# mycpu_monitor.net
KiCad netlist of a schematic drawn in EAGLE
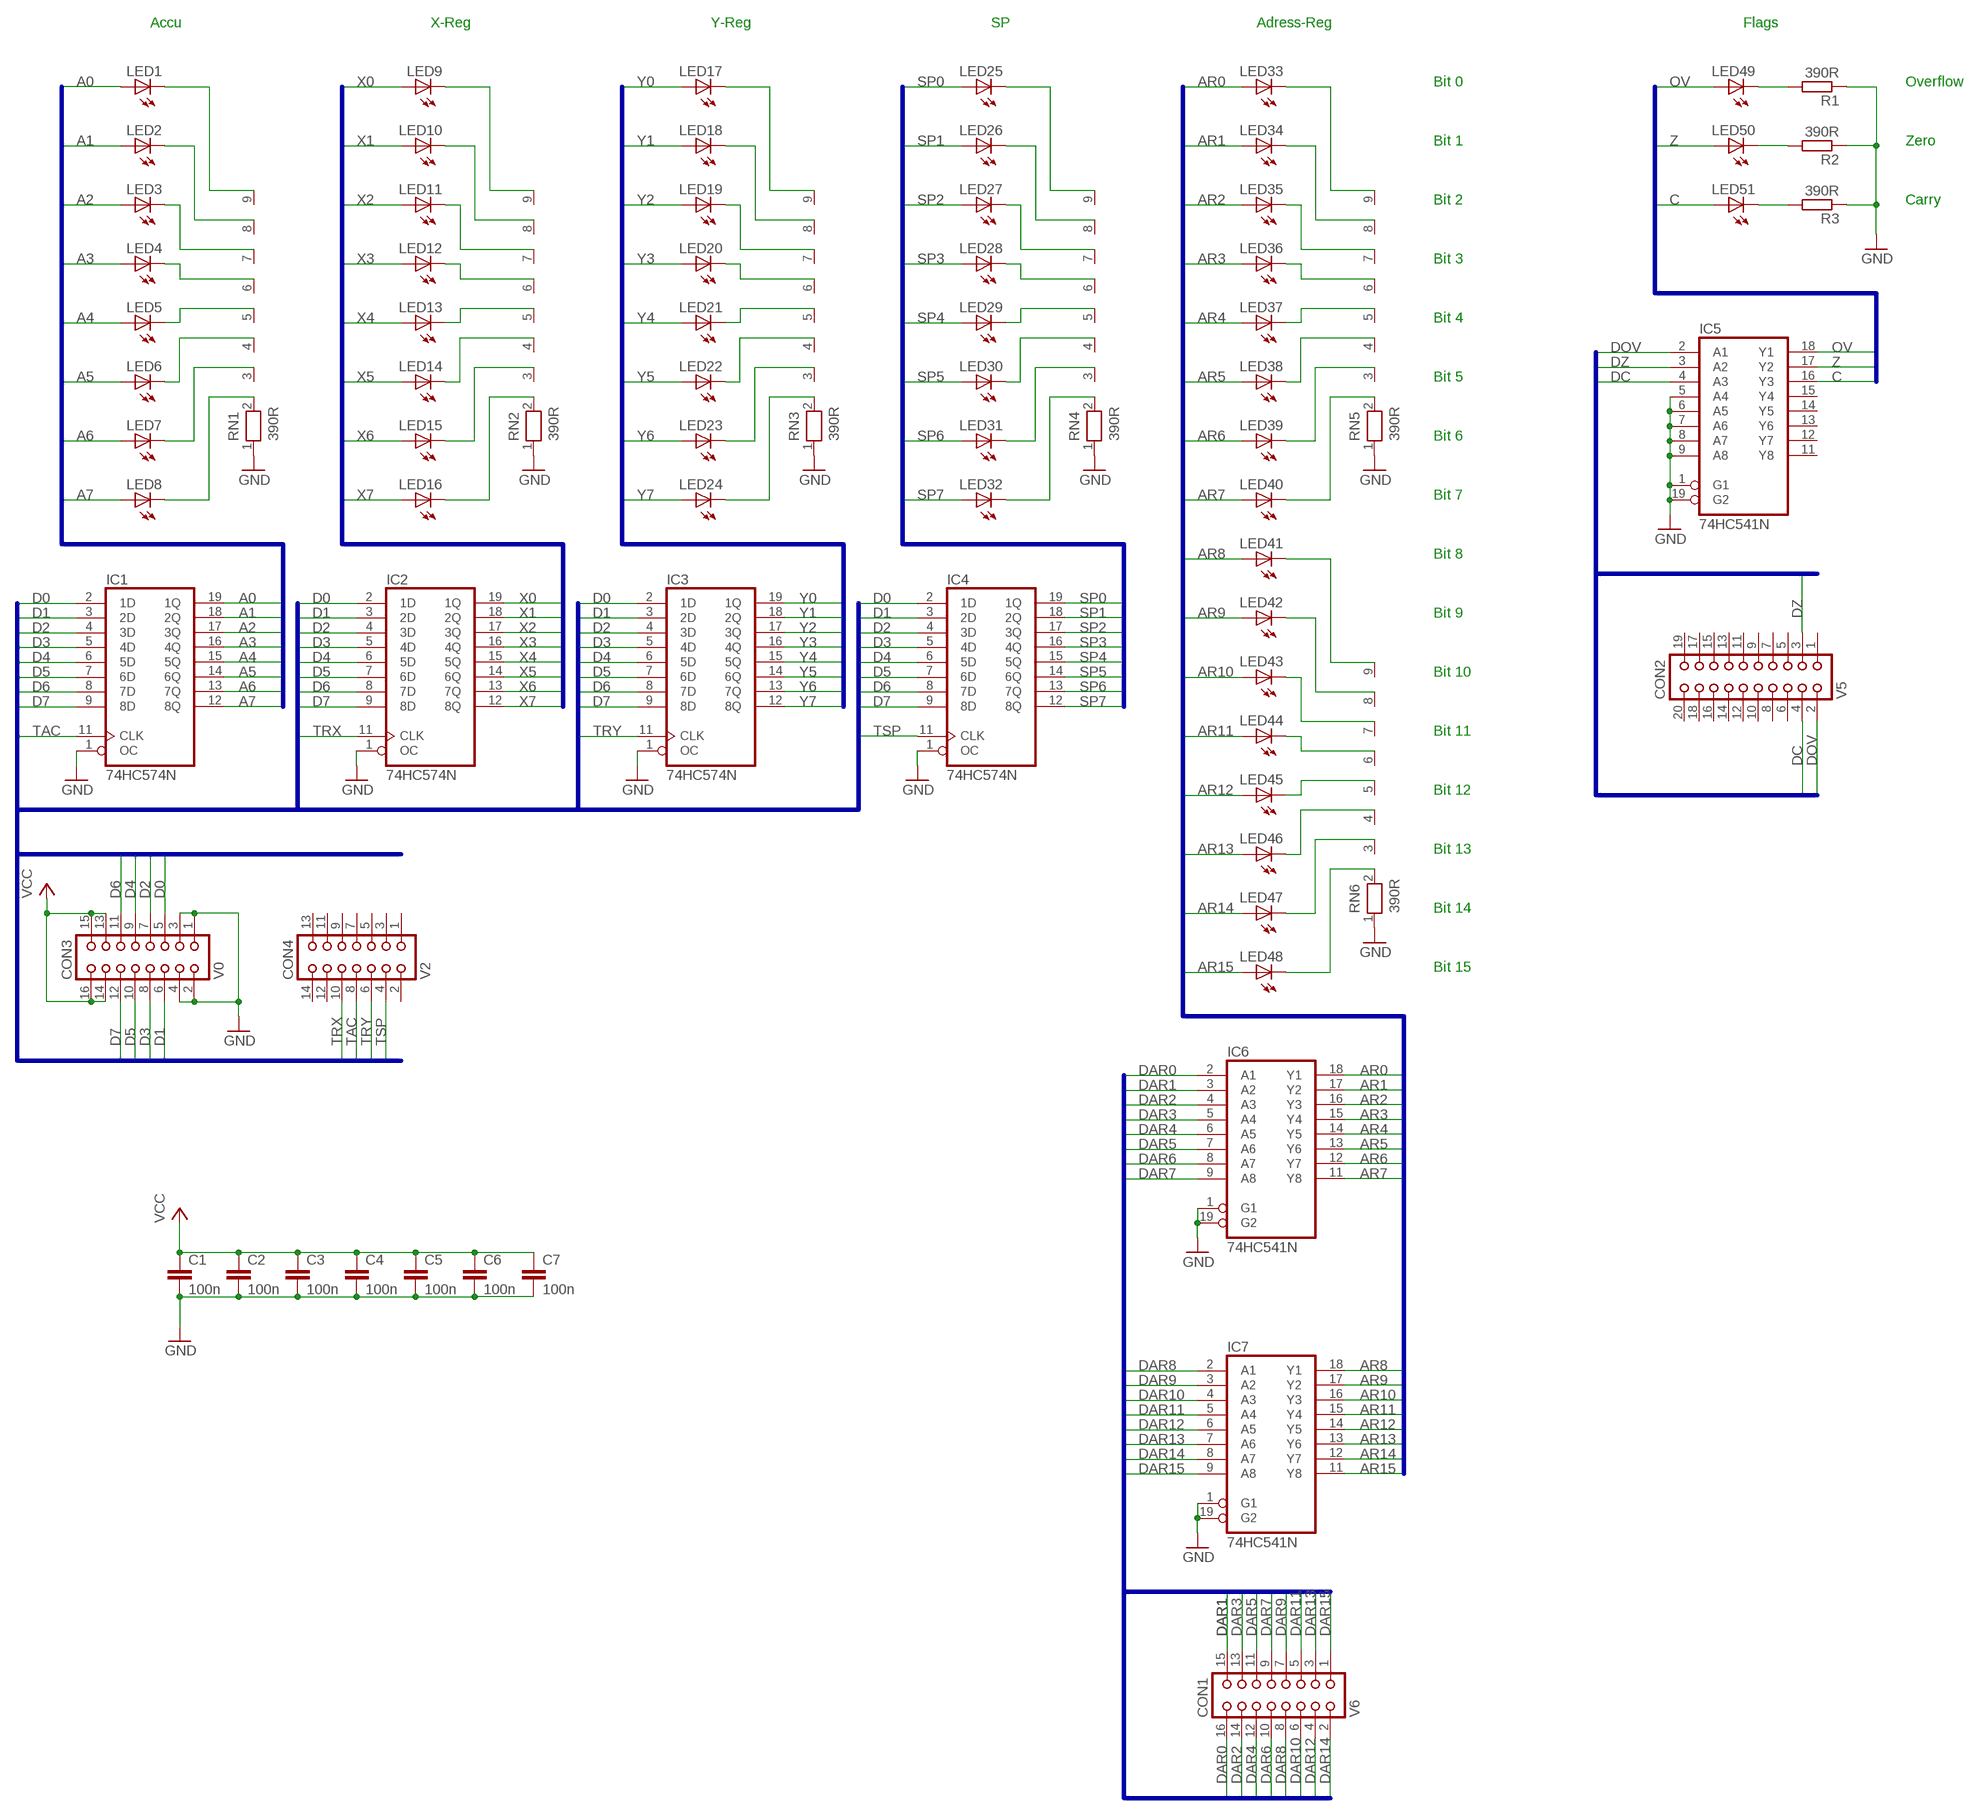
[diagram p0: schematic, sheet 1]

(export (version "E")
  (design (tool "Eeschema 10.0.6"))
  (components
    (comp (ref "C1")
      (value "100n")
      (footprint "eagle-import:C050-024X044")
      (libsource (lib "eagle-import") (part "C-EU050-024X044"))
    )
    (comp (ref "C2")
      (value "100n")
      (footprint "eagle-import:C050-024X044")
      (libsource (lib "eagle-import") (part "C-EU050-024X044"))
    )
    (comp (ref "C3")
      (value "100n")
      (footprint "eagle-import:C050-024X044")
      (libsource (lib "eagle-import") (part "C-EU050-024X044"))
    )
    (comp (ref "C4")
      (value "100n")
      (footprint "eagle-import:C050-024X044")
      (libsource (lib "eagle-import") (part "C-EU050-024X044"))
    )
    (comp (ref "C5")
      (value "100n")
      (footprint "eagle-import:C050-024X044")
      (libsource (lib "eagle-import") (part "C-EU050-024X044"))
    )
    (comp (ref "C6")
      (value "100n")
      (footprint "eagle-import:C050-024X044")
      (libsource (lib "eagle-import") (part "C-EU050-024X044"))
    )
    (comp (ref "C7")
      (value "100n")
      (footprint "eagle-import:C050-024X044")
      (libsource (lib "eagle-import") (part "C-EU050-024X044"))
    )
    (comp (ref "CON1")
      (value "V6")
      (footprint "eagle-import:CON16L")
      (libsource (lib "eagle-import") (part "CON16L"))
    )
    (comp (ref "CON2")
      (value "V5")
      (footprint "eagle-import:CON20L")
      (libsource (lib "eagle-import") (part "CON20L"))
    )
    (comp (ref "CON3")
      (value "V0")
      (footprint "eagle-import:CON16L")
      (libsource (lib "eagle-import") (part "CON16L"))
    )
    (comp (ref "CON4")
      (value "V2")
      (footprint "eagle-import:CON14L")
      (libsource (lib "eagle-import") (part "CON14L"))
    )
    (comp (ref "IC1")
      (value "74HC574N")
      (footprint "eagle-import:DIL20")
      (libsource (lib "eagle-import") (part "74574NHC"))
    )
    (comp (ref "IC2")
      (value "74HC574N")
      (footprint "eagle-import:DIL20")
      (libsource (lib "eagle-import") (part "74574NHC"))
    )
    (comp (ref "IC3")
      (value "74HC574N")
      (footprint "eagle-import:DIL20")
      (libsource (lib "eagle-import") (part "74574NHC"))
    )
    (comp (ref "IC4")
      (value "74HC574N")
      (footprint "eagle-import:DIL20")
      (libsource (lib "eagle-import") (part "74574NHC"))
    )
    (comp (ref "IC5")
      (value "74HC541N")
      (footprint "eagle-import:DIL20")
      (libsource (lib "eagle-import") (part "74541NHC"))
    )
    (comp (ref "IC6")
      (value "74HC541N")
      (footprint "eagle-import:DIL20")
      (libsource (lib "eagle-import") (part "74541NHC"))
    )
    (comp (ref "IC7")
      (value "74HC541N")
      (footprint "eagle-import:DIL20")
      (libsource (lib "eagle-import") (part "74541NHC"))
    )
    (comp (ref "LED1")
      (value "LED3MM")
      (footprint "eagle-import:LED3MM")
      (libsource (lib "eagle-import") (part "LED3MM"))
    )
    (comp (ref "LED2")
      (value "LED3MM")
      (footprint "eagle-import:LED3MM")
      (libsource (lib "eagle-import") (part "LED3MM"))
    )
    (comp (ref "LED3")
      (value "LED3MM")
      (footprint "eagle-import:LED3MM")
      (libsource (lib "eagle-import") (part "LED3MM"))
    )
    (comp (ref "LED4")
      (value "LED3MM")
      (footprint "eagle-import:LED3MM")
      (libsource (lib "eagle-import") (part "LED3MM"))
    )
    (comp (ref "LED5")
      (value "LED3MM")
      (footprint "eagle-import:LED3MM")
      (libsource (lib "eagle-import") (part "LED3MM"))
    )
    (comp (ref "LED6")
      (value "LED3MM")
      (footprint "eagle-import:LED3MM")
      (libsource (lib "eagle-import") (part "LED3MM"))
    )
    (comp (ref "LED7")
      (value "LED3MM")
      (footprint "eagle-import:LED3MM")
      (libsource (lib "eagle-import") (part "LED3MM"))
    )
    (comp (ref "LED8")
      (value "LED3MM")
      (footprint "eagle-import:LED3MM")
      (libsource (lib "eagle-import") (part "LED3MM"))
    )
    (comp (ref "LED9")
      (value "LED3MM")
      (footprint "eagle-import:LED3MM")
      (libsource (lib "eagle-import") (part "LED3MM"))
    )
    (comp (ref "LED10")
      (value "LED3MM")
      (footprint "eagle-import:LED3MM")
      (libsource (lib "eagle-import") (part "LED3MM"))
    )
    (comp (ref "LED11")
      (value "LED3MM")
      (footprint "eagle-import:LED3MM")
      (libsource (lib "eagle-import") (part "LED3MM"))
    )
    (comp (ref "LED12")
      (value "LED3MM")
      (footprint "eagle-import:LED3MM")
      (libsource (lib "eagle-import") (part "LED3MM"))
    )
    (comp (ref "LED13")
      (value "LED3MM")
      (footprint "eagle-import:LED3MM")
      (libsource (lib "eagle-import") (part "LED3MM"))
    )
    (comp (ref "LED14")
      (value "LED3MM")
      (footprint "eagle-import:LED3MM")
      (libsource (lib "eagle-import") (part "LED3MM"))
    )
    (comp (ref "LED15")
      (value "LED3MM")
      (footprint "eagle-import:LED3MM")
      (libsource (lib "eagle-import") (part "LED3MM"))
    )
    (comp (ref "LED16")
      (value "LED3MM")
      (footprint "eagle-import:LED3MM")
      (libsource (lib "eagle-import") (part "LED3MM"))
    )
    (comp (ref "LED17")
      (value "LED3MM")
      (footprint "eagle-import:LED3MM")
      (libsource (lib "eagle-import") (part "LED3MM"))
    )
    (comp (ref "LED18")
      (value "LED3MM")
      (footprint "eagle-import:LED3MM")
      (libsource (lib "eagle-import") (part "LED3MM"))
    )
    (comp (ref "LED19")
      (value "LED3MM")
      (footprint "eagle-import:LED3MM")
      (libsource (lib "eagle-import") (part "LED3MM"))
    )
    (comp (ref "LED20")
      (value "LED3MM")
      (footprint "eagle-import:LED3MM")
      (libsource (lib "eagle-import") (part "LED3MM"))
    )
    (comp (ref "LED21")
      (value "LED3MM")
      (footprint "eagle-import:LED3MM")
      (libsource (lib "eagle-import") (part "LED3MM"))
    )
    (comp (ref "LED22")
      (value "LED3MM")
      (footprint "eagle-import:LED3MM")
      (libsource (lib "eagle-import") (part "LED3MM"))
    )
    (comp (ref "LED23")
      (value "LED3MM")
      (footprint "eagle-import:LED3MM")
      (libsource (lib "eagle-import") (part "LED3MM"))
    )
    (comp (ref "LED24")
      (value "LED3MM")
      (footprint "eagle-import:LED3MM")
      (libsource (lib "eagle-import") (part "LED3MM"))
    )
    (comp (ref "LED25")
      (value "LED3MM")
      (footprint "eagle-import:LED3MM")
      (libsource (lib "eagle-import") (part "LED3MM"))
    )
    (comp (ref "LED26")
      (value "LED3MM")
      (footprint "eagle-import:LED3MM")
      (libsource (lib "eagle-import") (part "LED3MM"))
    )
    (comp (ref "LED27")
      (value "LED3MM")
      (footprint "eagle-import:LED3MM")
      (libsource (lib "eagle-import") (part "LED3MM"))
    )
    (comp (ref "LED28")
      (value "LED3MM")
      (footprint "eagle-import:LED3MM")
      (libsource (lib "eagle-import") (part "LED3MM"))
    )
    (comp (ref "LED29")
      (value "LED3MM")
      (footprint "eagle-import:LED3MM")
      (libsource (lib "eagle-import") (part "LED3MM"))
    )
    (comp (ref "LED30")
      (value "LED3MM")
      (footprint "eagle-import:LED3MM")
      (libsource (lib "eagle-import") (part "LED3MM"))
    )
    (comp (ref "LED31")
      (value "LED3MM")
      (footprint "eagle-import:LED3MM")
      (libsource (lib "eagle-import") (part "LED3MM"))
    )
    (comp (ref "LED32")
      (value "LED3MM")
      (footprint "eagle-import:LED3MM")
      (libsource (lib "eagle-import") (part "LED3MM"))
    )
    (comp (ref "LED33")
      (value "LED3MM")
      (footprint "eagle-import:LED3MM")
      (libsource (lib "eagle-import") (part "LED3MM"))
    )
    (comp (ref "LED34")
      (value "LED3MM")
      (footprint "eagle-import:LED3MM")
      (libsource (lib "eagle-import") (part "LED3MM"))
    )
    (comp (ref "LED35")
      (value "LED3MM")
      (footprint "eagle-import:LED3MM")
      (libsource (lib "eagle-import") (part "LED3MM"))
    )
    (comp (ref "LED36")
      (value "LED3MM")
      (footprint "eagle-import:LED3MM")
      (libsource (lib "eagle-import") (part "LED3MM"))
    )
    (comp (ref "LED37")
      (value "LED3MM")
      (footprint "eagle-import:LED3MM")
      (libsource (lib "eagle-import") (part "LED3MM"))
    )
    (comp (ref "LED38")
      (value "LED3MM")
      (footprint "eagle-import:LED3MM")
      (libsource (lib "eagle-import") (part "LED3MM"))
    )
    (comp (ref "LED39")
      (value "LED3MM")
      (footprint "eagle-import:LED3MM")
      (libsource (lib "eagle-import") (part "LED3MM"))
    )
    (comp (ref "LED40")
      (value "LED3MM")
      (footprint "eagle-import:LED3MM")
      (libsource (lib "eagle-import") (part "LED3MM"))
    )
    (comp (ref "LED41")
      (value "LED3MM")
      (footprint "eagle-import:LED3MM")
      (libsource (lib "eagle-import") (part "LED3MM"))
    )
    (comp (ref "LED42")
      (value "LED3MM")
      (footprint "eagle-import:LED3MM")
      (libsource (lib "eagle-import") (part "LED3MM"))
    )
    (comp (ref "LED43")
      (value "LED3MM")
      (footprint "eagle-import:LED3MM")
      (libsource (lib "eagle-import") (part "LED3MM"))
    )
    (comp (ref "LED44")
      (value "LED3MM")
      (footprint "eagle-import:LED3MM")
      (libsource (lib "eagle-import") (part "LED3MM"))
    )
    (comp (ref "LED45")
      (value "LED3MM")
      (footprint "eagle-import:LED3MM")
      (libsource (lib "eagle-import") (part "LED3MM"))
    )
    (comp (ref "LED46")
      (value "LED3MM")
      (footprint "eagle-import:LED3MM")
      (libsource (lib "eagle-import") (part "LED3MM"))
    )
    (comp (ref "LED47")
      (value "LED3MM")
      (footprint "eagle-import:LED3MM")
      (libsource (lib "eagle-import") (part "LED3MM"))
    )
    (comp (ref "LED48")
      (value "LED3MM")
      (footprint "eagle-import:LED3MM")
      (libsource (lib "eagle-import") (part "LED3MM"))
    )
    (comp (ref "LED49")
      (value "LED3MM")
      (footprint "eagle-import:LED3MM")
      (libsource (lib "eagle-import") (part "LED3MM"))
    )
    (comp (ref "LED50")
      (value "LED3MM")
      (footprint "eagle-import:LED3MM")
      (libsource (lib "eagle-import") (part "LED3MM"))
    )
    (comp (ref "LED51")
      (value "LED3MM")
      (footprint "eagle-import:LED3MM")
      (libsource (lib "eagle-import") (part "LED3MM"))
    )
    (comp (ref "R1")
      (value "390R")
      (footprint "eagle-import:0207_7")
      (libsource (lib "eagle-import") (part "R-EU_0207/7"))
    )
    (comp (ref "R2")
      (value "390R")
      (footprint "eagle-import:0207_7")
      (libsource (lib "eagle-import") (part "R-EU_0207/7"))
    )
    (comp (ref "R3")
      (value "390R")
      (footprint "eagle-import:0207_7")
      (libsource (lib "eagle-import") (part "R-EU_0207/7"))
    )
    (comp (ref "RN1")
      (value "390R")
      (footprint "eagle-import:RN-9")
      (libsource (lib "eagle-import") (part "RN08"))
    )
    (comp (ref "RN2")
      (value "390R")
      (footprint "eagle-import:RN-9")
      (libsource (lib "eagle-import") (part "RN08"))
    )
    (comp (ref "RN3")
      (value "390R")
      (footprint "eagle-import:RN-9")
      (libsource (lib "eagle-import") (part "RN08"))
    )
    (comp (ref "RN4")
      (value "390R")
      (footprint "eagle-import:RN-9")
      (libsource (lib "eagle-import") (part "RN08"))
    )
    (comp (ref "RN5")
      (value "390R")
      (footprint "eagle-import:RN-9")
      (libsource (lib "eagle-import") (part "RN08"))
    )
    (comp (ref "RN6")
      (value "390R")
      (footprint "eagle-import:RN-9")
      (libsource (lib "eagle-import") (part "RN08"))
    )
  )
  (nets
    (net (code "1") (name "/A0") (class "Default")
      (node (ref "IC1") (pin "19") (pinfunction "1Q_19") (pintype "tri_state"))
      (node (ref "LED1") (pin "A") (pinfunction "A_A") (pintype "passive"))
    )
    (net (code "2") (name "/A1") (class "Default")
      (node (ref "IC1") (pin "18") (pinfunction "2Q_18") (pintype "tri_state"))
      (node (ref "LED2") (pin "A") (pinfunction "A_A") (pintype "passive"))
    )
    (net (code "3") (name "/A2") (class "Default")
      (node (ref "IC1") (pin "17") (pinfunction "3Q_17") (pintype "tri_state"))
      (node (ref "LED3") (pin "A") (pinfunction "A_A") (pintype "passive"))
    )
    (net (code "4") (name "/A3") (class "Default")
      (node (ref "IC1") (pin "16") (pinfunction "4Q_16") (pintype "tri_state"))
      (node (ref "LED4") (pin "A") (pinfunction "A_A") (pintype "passive"))
    )
    (net (code "5") (name "/A4") (class "Default")
      (node (ref "IC1") (pin "15") (pinfunction "5Q_15") (pintype "tri_state"))
      (node (ref "LED5") (pin "A") (pinfunction "A_A") (pintype "passive"))
    )
    (net (code "6") (name "/A5") (class "Default")
      (node (ref "IC1") (pin "14") (pinfunction "6Q_14") (pintype "tri_state"))
      (node (ref "LED6") (pin "A") (pinfunction "A_A") (pintype "passive"))
    )
    (net (code "7") (name "/A6") (class "Default")
      (node (ref "IC1") (pin "13") (pinfunction "7Q_13") (pintype "tri_state"))
      (node (ref "LED7") (pin "A") (pinfunction "A_A") (pintype "passive"))
    )
    (net (code "8") (name "/A7") (class "Default")
      (node (ref "IC1") (pin "12") (pinfunction "8Q_12") (pintype "tri_state"))
      (node (ref "LED8") (pin "A") (pinfunction "A_A") (pintype "passive"))
    )
    (net (code "9") (name "/AR0") (class "Default")
      (node (ref "IC6") (pin "18") (pinfunction "Y1_18") (pintype "tri_state"))
      (node (ref "LED33") (pin "A") (pinfunction "A_A") (pintype "passive"))
    )
    (net (code "10") (name "/AR1") (class "Default")
      (node (ref "IC6") (pin "17") (pinfunction "Y2_17") (pintype "tri_state"))
      (node (ref "LED34") (pin "A") (pinfunction "A_A") (pintype "passive"))
    )
    (net (code "11") (name "/AR2") (class "Default")
      (node (ref "IC6") (pin "16") (pinfunction "Y3_16") (pintype "tri_state"))
      (node (ref "LED35") (pin "A") (pinfunction "A_A") (pintype "passive"))
    )
    (net (code "12") (name "/AR3") (class "Default")
      (node (ref "IC6") (pin "15") (pinfunction "Y4_15") (pintype "tri_state"))
      (node (ref "LED36") (pin "A") (pinfunction "A_A") (pintype "passive"))
    )
    (net (code "13") (name "/AR4") (class "Default")
      (node (ref "IC6") (pin "14") (pinfunction "Y5_14") (pintype "tri_state"))
      (node (ref "LED37") (pin "A") (pinfunction "A_A") (pintype "passive"))
    )
    (net (code "14") (name "/AR5") (class "Default")
      (node (ref "IC6") (pin "13") (pinfunction "Y6_13") (pintype "tri_state"))
      (node (ref "LED38") (pin "A") (pinfunction "A_A") (pintype "passive"))
    )
    (net (code "15") (name "/AR6") (class "Default")
      (node (ref "IC6") (pin "12") (pinfunction "Y7_12") (pintype "tri_state"))
      (node (ref "LED39") (pin "A") (pinfunction "A_A") (pintype "passive"))
    )
    (net (code "16") (name "/AR7") (class "Default")
      (node (ref "IC6") (pin "11") (pinfunction "Y8_11") (pintype "tri_state"))
      (node (ref "LED40") (pin "A") (pinfunction "A_A") (pintype "passive"))
    )
    (net (code "17") (name "/AR8") (class "Default")
      (node (ref "IC7") (pin "18") (pinfunction "Y1_18") (pintype "tri_state"))
      (node (ref "LED41") (pin "A") (pinfunction "A_A") (pintype "passive"))
    )
    (net (code "18") (name "/AR9") (class "Default")
      (node (ref "IC7") (pin "17") (pinfunction "Y2_17") (pintype "tri_state"))
      (node (ref "LED42") (pin "A") (pinfunction "A_A") (pintype "passive"))
    )
    (net (code "19") (name "/AR10") (class "Default")
      (node (ref "IC7") (pin "16") (pinfunction "Y3_16") (pintype "tri_state"))
      (node (ref "LED43") (pin "A") (pinfunction "A_A") (pintype "passive"))
    )
    (net (code "20") (name "/AR11") (class "Default")
      (node (ref "IC7") (pin "15") (pinfunction "Y4_15") (pintype "tri_state"))
      (node (ref "LED44") (pin "A") (pinfunction "A_A") (pintype "passive"))
    )
    (net (code "21") (name "/AR12") (class "Default")
      (node (ref "IC7") (pin "14") (pinfunction "Y5_14") (pintype "tri_state"))
      (node (ref "LED45") (pin "A") (pinfunction "A_A") (pintype "passive"))
    )
    (net (code "22") (name "/AR13") (class "Default")
      (node (ref "IC7") (pin "13") (pinfunction "Y6_13") (pintype "tri_state"))
      (node (ref "LED46") (pin "A") (pinfunction "A_A") (pintype "passive"))
    )
    (net (code "23") (name "/AR14") (class "Default")
      (node (ref "IC7") (pin "12") (pinfunction "Y7_12") (pintype "tri_state"))
      (node (ref "LED47") (pin "A") (pinfunction "A_A") (pintype "passive"))
    )
    (net (code "24") (name "/AR15") (class "Default")
      (node (ref "IC7") (pin "11") (pinfunction "Y8_11") (pintype "tri_state"))
      (node (ref "LED48") (pin "A") (pinfunction "A_A") (pintype "passive"))
    )
    (net (code "25") (name "/C") (class "Default")
      (node (ref "IC5") (pin "16") (pinfunction "Y3_16") (pintype "tri_state"))
      (node (ref "LED51") (pin "A") (pinfunction "A_A") (pintype "passive"))
    )
    (net (code "26") (name "/D0") (class "Default")
      (node (ref "CON3") (pin "5") (pinfunction "5_5") (pintype "passive"))
      (node (ref "IC1") (pin "2") (pinfunction "1D_2") (pintype "input"))
      (node (ref "IC2") (pin "2") (pinfunction "1D_2") (pintype "input"))
      (node (ref "IC3") (pin "2") (pinfunction "1D_2") (pintype "input"))
      (node (ref "IC4") (pin "2") (pinfunction "1D_2") (pintype "input"))
    )
    (net (code "27") (name "/D1") (class "Default")
      (node (ref "CON3") (pin "6") (pinfunction "6_6") (pintype "passive"))
      (node (ref "IC1") (pin "3") (pinfunction "2D_3") (pintype "input"))
      (node (ref "IC2") (pin "3") (pinfunction "2D_3") (pintype "input"))
      (node (ref "IC3") (pin "3") (pinfunction "2D_3") (pintype "input"))
      (node (ref "IC4") (pin "3") (pinfunction "2D_3") (pintype "input"))
    )
    (net (code "28") (name "/D2") (class "Default")
      (node (ref "CON3") (pin "7") (pinfunction "7_7") (pintype "passive"))
      (node (ref "IC1") (pin "4") (pinfunction "3D_4") (pintype "input"))
      (node (ref "IC2") (pin "4") (pinfunction "3D_4") (pintype "input"))
      (node (ref "IC3") (pin "4") (pinfunction "3D_4") (pintype "input"))
      (node (ref "IC4") (pin "4") (pinfunction "3D_4") (pintype "input"))
    )
    (net (code "29") (name "/D3") (class "Default")
      (node (ref "CON3") (pin "8") (pinfunction "8_8") (pintype "passive"))
      (node (ref "IC1") (pin "5") (pinfunction "4D_5") (pintype "input"))
      (node (ref "IC2") (pin "5") (pinfunction "4D_5") (pintype "input"))
      (node (ref "IC3") (pin "5") (pinfunction "4D_5") (pintype "input"))
      (node (ref "IC4") (pin "5") (pinfunction "4D_5") (pintype "input"))
    )
    (net (code "30") (name "/D4") (class "Default")
      (node (ref "CON3") (pin "9") (pinfunction "9_9") (pintype "passive"))
      (node (ref "IC1") (pin "6") (pinfunction "5D_6") (pintype "input"))
      (node (ref "IC2") (pin "6") (pinfunction "5D_6") (pintype "input"))
      (node (ref "IC3") (pin "6") (pinfunction "5D_6") (pintype "input"))
      (node (ref "IC4") (pin "6") (pinfunction "5D_6") (pintype "input"))
    )
    (net (code "31") (name "/D5") (class "Default")
      (node (ref "CON3") (pin "10") (pinfunction "10_10") (pintype "passive"))
      (node (ref "IC1") (pin "7") (pinfunction "6D_7") (pintype "input"))
      (node (ref "IC2") (pin "7") (pinfunction "6D_7") (pintype "input"))
      (node (ref "IC3") (pin "7") (pinfunction "6D_7") (pintype "input"))
      (node (ref "IC4") (pin "7") (pinfunction "6D_7") (pintype "input"))
    )
    (net (code "32") (name "/D6") (class "Default")
      (node (ref "CON3") (pin "11") (pinfunction "11_11") (pintype "passive"))
      (node (ref "IC1") (pin "8") (pinfunction "7D_8") (pintype "input"))
      (node (ref "IC2") (pin "8") (pinfunction "7D_8") (pintype "input"))
      (node (ref "IC3") (pin "8") (pinfunction "7D_8") (pintype "input"))
      (node (ref "IC4") (pin "8") (pinfunction "7D_8") (pintype "input"))
    )
    (net (code "33") (name "/D7") (class "Default")
      (node (ref "CON3") (pin "12") (pinfunction "12_12") (pintype "passive"))
      (node (ref "IC1") (pin "9") (pinfunction "8D_9") (pintype "input"))
      (node (ref "IC2") (pin "9") (pinfunction "8D_9") (pintype "input"))
      (node (ref "IC3") (pin "9") (pinfunction "8D_9") (pintype "input"))
      (node (ref "IC4") (pin "9") (pinfunction "8D_9") (pintype "input"))
    )
    (net (code "34") (name "/DAR0") (class "Default")
      (node (ref "CON1") (pin "16") (pinfunction "16_16") (pintype "passive"))
      (node (ref "IC6") (pin "2") (pinfunction "A1_2") (pintype "input"))
    )
    (net (code "35") (name "/DAR1") (class "Default")
      (node (ref "CON1") (pin "15") (pinfunction "15_15") (pintype "passive"))
      (node (ref "IC6") (pin "3") (pinfunction "A2_3") (pintype "input"))
    )
    (net (code "36") (name "/DAR2") (class "Default")
      (node (ref "CON1") (pin "14") (pinfunction "14_14") (pintype "passive"))
      (node (ref "IC6") (pin "4") (pinfunction "A3_4") (pintype "input"))
    )
    (net (code "37") (name "/DAR3") (class "Default")
      (node (ref "CON1") (pin "13") (pinfunction "13_13") (pintype "passive"))
      (node (ref "IC6") (pin "5") (pinfunction "A4_5") (pintype "input"))
    )
    (net (code "38") (name "/DAR4") (class "Default")
      (node (ref "CON1") (pin "12") (pinfunction "12_12") (pintype "passive"))
      (node (ref "IC6") (pin "6") (pinfunction "A5_6") (pintype "input"))
    )
    (net (code "39") (name "/DAR5") (class "Default")
      (node (ref "CON1") (pin "11") (pinfunction "11_11") (pintype "passive"))
      (node (ref "IC6") (pin "7") (pinfunction "A6_7") (pintype "input"))
    )
    (net (code "40") (name "/DAR6") (class "Default")
      (node (ref "CON1") (pin "10") (pinfunction "10_10") (pintype "passive"))
      (node (ref "IC6") (pin "8") (pinfunction "A7_8") (pintype "input"))
    )
    (net (code "41") (name "/DAR7") (class "Default")
      (node (ref "CON1") (pin "9") (pinfunction "9_9") (pintype "passive"))
      (node (ref "IC6") (pin "9") (pinfunction "A8_9") (pintype "input"))
    )
    (net (code "42") (name "/DAR8") (class "Default")
      (node (ref "CON1") (pin "8") (pinfunction "8_8") (pintype "passive"))
      (node (ref "IC7") (pin "2") (pinfunction "A1_2") (pintype "input"))
    )
    (net (code "43") (name "/DAR9") (class "Default")
      (node (ref "CON1") (pin "7") (pinfunction "7_7") (pintype "passive"))
      (node (ref "IC7") (pin "3") (pinfunction "A2_3") (pintype "input"))
    )
    (net (code "44") (name "/DAR10") (class "Default")
      (node (ref "CON1") (pin "6") (pinfunction "6_6") (pintype "passive"))
      (node (ref "IC7") (pin "4") (pinfunction "A3_4") (pintype "input"))
    )
    (net (code "45") (name "/DAR11") (class "Default")
      (node (ref "CON1") (pin "5") (pinfunction "5_5") (pintype "passive"))
      (node (ref "IC7") (pin "5") (pinfunction "A4_5") (pintype "input"))
    )
    (net (code "46") (name "/DAR12") (class "Default")
      (node (ref "CON1") (pin "4") (pinfunction "4_4") (pintype "passive"))
      (node (ref "IC7") (pin "6") (pinfunction "A5_6") (pintype "input"))
    )
    (net (code "47") (name "/DAR13") (class "Default")
      (node (ref "CON1") (pin "3") (pinfunction "3_3") (pintype "passive"))
      (node (ref "IC7") (pin "7") (pinfunction "A6_7") (pintype "input"))
    )
    (net (code "48") (name "/DAR14") (class "Default")
      (node (ref "CON1") (pin "2") (pinfunction "2_2") (pintype "passive"))
      (node (ref "IC7") (pin "8") (pinfunction "A7_8") (pintype "input"))
    )
    (net (code "49") (name "/DAR15") (class "Default")
      (node (ref "CON1") (pin "1") (pinfunction "1_1") (pintype "passive"))
      (node (ref "IC7") (pin "9") (pinfunction "A8_9") (pintype "input"))
    )
    (net (code "50") (name "/DC") (class "Default")
      (node (ref "CON2") (pin "4") (pinfunction "4_4") (pintype "passive"))
      (node (ref "IC5") (pin "4") (pinfunction "A3_4") (pintype "input"))
    )
    (net (code "51") (name "/DOV") (class "Default")
      (node (ref "CON2") (pin "2") (pinfunction "2_2") (pintype "passive"))
      (node (ref "IC5") (pin "2") (pinfunction "A1_2") (pintype "input"))
    )
    (net (code "52") (name "/DZ") (class "Default")
      (node (ref "CON2") (pin "3") (pinfunction "3_3") (pintype "passive"))
      (node (ref "IC5") (pin "3") (pinfunction "A2_3") (pintype "input"))
    )
    (net (code "53") (name "/OV") (class "Default")
      (node (ref "IC5") (pin "18") (pinfunction "Y1_18") (pintype "tri_state"))
      (node (ref "LED49") (pin "A") (pinfunction "A_A") (pintype "passive"))
    )
    (net (code "54") (name "/SP0") (class "Default")
      (node (ref "IC4") (pin "19") (pinfunction "1Q_19") (pintype "tri_state"))
      (node (ref "LED25") (pin "A") (pinfunction "A_A") (pintype "passive"))
    )
    (net (code "55") (name "/SP1") (class "Default")
      (node (ref "IC4") (pin "18") (pinfunction "2Q_18") (pintype "tri_state"))
      (node (ref "LED26") (pin "A") (pinfunction "A_A") (pintype "passive"))
    )
    (net (code "56") (name "/SP2") (class "Default")
      (node (ref "IC4") (pin "17") (pinfunction "3Q_17") (pintype "tri_state"))
      (node (ref "LED27") (pin "A") (pinfunction "A_A") (pintype "passive"))
    )
    (net (code "57") (name "/SP3") (class "Default")
      (node (ref "IC4") (pin "16") (pinfunction "4Q_16") (pintype "tri_state"))
      (node (ref "LED28") (pin "A") (pinfunction "A_A") (pintype "passive"))
    )
    (net (code "58") (name "/SP4") (class "Default")
      (node (ref "IC4") (pin "15") (pinfunction "5Q_15") (pintype "tri_state"))
      (node (ref "LED29") (pin "A") (pinfunction "A_A") (pintype "passive"))
    )
    (net (code "59") (name "/SP5") (class "Default")
      (node (ref "IC4") (pin "14") (pinfunction "6Q_14") (pintype "tri_state"))
      (node (ref "LED30") (pin "A") (pinfunction "A_A") (pintype "passive"))
    )
    (net (code "60") (name "/SP6") (class "Default")
      (node (ref "IC4") (pin "13") (pinfunction "7Q_13") (pintype "tri_state"))
      (node (ref "LED31") (pin "A") (pinfunction "A_A") (pintype "passive"))
    )
    (net (code "61") (name "/SP7") (class "Default")
      (node (ref "IC4") (pin "12") (pinfunction "8Q_12") (pintype "tri_state"))
      (node (ref "LED32") (pin "A") (pinfunction "A_A") (pintype "passive"))
    )
    (net (code "62") (name "/TAC") (class "Default")
      (node (ref "CON4") (pin "8") (pinfunction "8_8") (pintype "passive"))
      (node (ref "IC1") (pin "11") (pinfunction "CLK_11") (pintype "input"))
    )
    (net (code "63") (name "/TRX") (class "Default")
      (node (ref "CON4") (pin "10") (pinfunction "10_10") (pintype "passive"))
      (node (ref "IC2") (pin "11") (pinfunction "CLK_11") (pintype "input"))
    )
    (net (code "64") (name "/TRY") (class "Default")
      (node (ref "CON4") (pin "6") (pinfunction "6_6") (pintype "passive"))
      (node (ref "IC3") (pin "11") (pinfunction "CLK_11") (pintype "input"))
    )
    (net (code "65") (name "/TSP") (class "Default")
      (node (ref "CON4") (pin "4") (pinfunction "4_4") (pintype "passive"))
      (node (ref "IC4") (pin "11") (pinfunction "CLK_11") (pintype "input"))
    )
    (net (code "66") (name "/X0") (class "Default")
      (node (ref "IC2") (pin "19") (pinfunction "1Q_19") (pintype "tri_state"))
      (node (ref "LED9") (pin "A") (pinfunction "A_A") (pintype "passive"))
    )
    (net (code "67") (name "/X1") (class "Default")
      (node (ref "IC2") (pin "18") (pinfunction "2Q_18") (pintype "tri_state"))
      (node (ref "LED10") (pin "A") (pinfunction "A_A") (pintype "passive"))
    )
    (net (code "68") (name "/X2") (class "Default")
      (node (ref "IC2") (pin "17") (pinfunction "3Q_17") (pintype "tri_state"))
      (node (ref "LED11") (pin "A") (pinfunction "A_A") (pintype "passive"))
    )
    (net (code "69") (name "/X3") (class "Default")
      (node (ref "IC2") (pin "16") (pinfunction "4Q_16") (pintype "tri_state"))
      (node (ref "LED12") (pin "A") (pinfunction "A_A") (pintype "passive"))
    )
    (net (code "70") (name "/X4") (class "Default")
      (node (ref "IC2") (pin "15") (pinfunction "5Q_15") (pintype "tri_state"))
      (node (ref "LED13") (pin "A") (pinfunction "A_A") (pintype "passive"))
    )
    (net (code "71") (name "/X5") (class "Default")
      (node (ref "IC2") (pin "14") (pinfunction "6Q_14") (pintype "tri_state"))
      (node (ref "LED14") (pin "A") (pinfunction "A_A") (pintype "passive"))
    )
    (net (code "72") (name "/X6") (class "Default")
      (node (ref "IC2") (pin "13") (pinfunction "7Q_13") (pintype "tri_state"))
      (node (ref "LED15") (pin "A") (pinfunction "A_A") (pintype "passive"))
    )
    (net (code "73") (name "/X7") (class "Default")
      (node (ref "IC2") (pin "12") (pinfunction "8Q_12") (pintype "tri_state"))
      (node (ref "LED16") (pin "A") (pinfunction "A_A") (pintype "passive"))
    )
    (net (code "74") (name "/Y0") (class "Default")
      (node (ref "IC3") (pin "19") (pinfunction "1Q_19") (pintype "tri_state"))
      (node (ref "LED17") (pin "A") (pinfunction "A_A") (pintype "passive"))
    )
    (net (code "75") (name "/Y1") (class "Default")
      (node (ref "IC3") (pin "18") (pinfunction "2Q_18") (pintype "tri_state"))
      (node (ref "LED18") (pin "A") (pinfunction "A_A") (pintype "passive"))
    )
    (net (code "76") (name "/Y2") (class "Default")
      (node (ref "IC3") (pin "17") (pinfunction "3Q_17") (pintype "tri_state"))
      (node (ref "LED19") (pin "A") (pinfunction "A_A") (pintype "passive"))
    )
    (net (code "77") (name "/Y3") (class "Default")
      (node (ref "IC3") (pin "16") (pinfunction "4Q_16") (pintype "tri_state"))
      (node (ref "LED20") (pin "A") (pinfunction "A_A") (pintype "passive"))
    )
    (net (code "78") (name "/Y4") (class "Default")
      (node (ref "IC3") (pin "15") (pinfunction "5Q_15") (pintype "tri_state"))
      (node (ref "LED21") (pin "A") (pinfunction "A_A") (pintype "passive"))
    )
    (net (code "79") (name "/Y5") (class "Default")
      (node (ref "IC3") (pin "14") (pinfunction "6Q_14") (pintype "tri_state"))
      (node (ref "LED22") (pin "A") (pinfunction "A_A") (pintype "passive"))
    )
    (net (code "80") (name "/Y6") (class "Default")
      (node (ref "IC3") (pin "13") (pinfunction "7Q_13") (pintype "tri_state"))
      (node (ref "LED23") (pin "A") (pinfunction "A_A") (pintype "passive"))
    )
    (net (code "81") (name "/Y7") (class "Default")
      (node (ref "IC3") (pin "12") (pinfunction "8Q_12") (pintype "tri_state"))
      (node (ref "LED24") (pin "A") (pinfunction "A_A") (pintype "passive"))
    )
    (net (code "82") (name "/Z") (class "Default")
      (node (ref "IC5") (pin "17") (pinfunction "Y2_17") (pintype "tri_state"))
      (node (ref "LED50") (pin "A") (pinfunction "A_A") (pintype "passive"))
    )
    (net (code "83") (name "GND") (class "Default")
      (node (ref "C1") (pin "2") (pinfunction "2_2") (pintype "passive"))
      (node (ref "C2") (pin "2") (pinfunction "2_2") (pintype "passive"))
      (node (ref "C3") (pin "2") (pinfunction "2_2") (pintype "passive"))
      (node (ref "C4") (pin "2") (pinfunction "2_2") (pintype "passive"))
      (node (ref "C5") (pin "2") (pinfunction "2_2") (pintype "passive"))
      (node (ref "C6") (pin "2") (pinfunction "2_2") (pintype "passive"))
      (node (ref "C7") (pin "2") (pinfunction "2_2") (pintype "passive"))
      (node (ref "CON3") (pin "1") (pinfunction "1_1") (pintype "passive"))
      (node (ref "CON3") (pin "2") (pinfunction "2_2") (pintype "passive"))
      (node (ref "CON3") (pin "3") (pinfunction "3_3") (pintype "passive"))
      (node (ref "CON3") (pin "4") (pinfunction "4_4") (pintype "passive"))
      (node (ref "IC1") (pin "1") (pinfunction "OC_1") (pintype "input"))
      (node (ref "IC2") (pin "1") (pinfunction "OC_1") (pintype "input"))
      (node (ref "IC3") (pin "1") (pinfunction "OC_1") (pintype "input"))
      (node (ref "IC4") (pin "1") (pinfunction "OC_1") (pintype "input"))
      (node (ref "IC5") (pin "1") (pinfunction "G1_1") (pintype "input"))
      (node (ref "IC5") (pin "19") (pinfunction "G2_19") (pintype "input"))
      (node (ref "IC5") (pin "5") (pinfunction "A4_5") (pintype "input"))
      (node (ref "IC5") (pin "6") (pinfunction "A5_6") (pintype "input"))
      (node (ref "IC5") (pin "7") (pinfunction "A6_7") (pintype "input"))
      (node (ref "IC5") (pin "8") (pinfunction "A7_8") (pintype "input"))
      (node (ref "IC5") (pin "9") (pinfunction "A8_9") (pintype "input"))
      (node (ref "IC6") (pin "1") (pinfunction "G1_1") (pintype "input"))
      (node (ref "IC6") (pin "19") (pinfunction "G2_19") (pintype "input"))
      (node (ref "IC7") (pin "1") (pinfunction "G1_1") (pintype "input"))
      (node (ref "IC7") (pin "19") (pinfunction "G2_19") (pintype "input"))
      (node (ref "R1") (pin "1") (pinfunction "1_1") (pintype "passive"))
      (node (ref "R2") (pin "1") (pinfunction "1_1") (pintype "passive"))
      (node (ref "R3") (pin "1") (pinfunction "1_1") (pintype "passive"))
      (node (ref "RN1") (pin "1") (pinfunction "1_1") (pintype "passive"))
      (node (ref "RN2") (pin "1") (pinfunction "1_1") (pintype "passive"))
      (node (ref "RN3") (pin "1") (pinfunction "1_1") (pintype "passive"))
      (node (ref "RN4") (pin "1") (pinfunction "1_1") (pintype "passive"))
      (node (ref "RN5") (pin "1") (pinfunction "1_1") (pintype "passive"))
      (node (ref "RN6") (pin "1") (pinfunction "1_1") (pintype "passive"))
    )
    (net (code "84") (name "Net-(LED1-C)") (class "Default")
      (node (ref "LED1") (pin "K") (pinfunction "C_K") (pintype "passive"))
      (node (ref "RN1") (pin "9") (pinfunction "9_9") (pintype "passive"))
    )
    (net (code "85") (name "Net-(LED2-C)") (class "Default")
      (node (ref "LED2") (pin "K") (pinfunction "C_K") (pintype "passive"))
      (node (ref "RN1") (pin "8") (pinfunction "8_8") (pintype "passive"))
    )
    (net (code "86") (name "Net-(LED3-C)") (class "Default")
      (node (ref "LED3") (pin "K") (pinfunction "C_K") (pintype "passive"))
      (node (ref "RN1") (pin "7") (pinfunction "7_7") (pintype "passive"))
    )
    (net (code "87") (name "Net-(LED4-C)") (class "Default")
      (node (ref "LED4") (pin "K") (pinfunction "C_K") (pintype "passive"))
      (node (ref "RN1") (pin "6") (pinfunction "6_6") (pintype "passive"))
    )
    (net (code "88") (name "Net-(LED5-C)") (class "Default")
      (node (ref "LED5") (pin "K") (pinfunction "C_K") (pintype "passive"))
      (node (ref "RN1") (pin "5") (pinfunction "5_5") (pintype "passive"))
    )
    (net (code "89") (name "Net-(LED6-C)") (class "Default")
      (node (ref "LED6") (pin "K") (pinfunction "C_K") (pintype "passive"))
      (node (ref "RN1") (pin "4") (pinfunction "4_4") (pintype "passive"))
    )
    (net (code "90") (name "Net-(LED7-C)") (class "Default")
      (node (ref "LED7") (pin "K") (pinfunction "C_K") (pintype "passive"))
      (node (ref "RN1") (pin "3") (pinfunction "3_3") (pintype "passive"))
    )
    (net (code "91") (name "Net-(LED8-C)") (class "Default")
      (node (ref "LED8") (pin "K") (pinfunction "C_K") (pintype "passive"))
      (node (ref "RN1") (pin "2") (pinfunction "2_2") (pintype "passive"))
    )
    (net (code "92") (name "Net-(LED9-C)") (class "Default")
      (node (ref "LED9") (pin "K") (pinfunction "C_K") (pintype "passive"))
      (node (ref "RN2") (pin "9") (pinfunction "9_9") (pintype "passive"))
    )
    (net (code "93") (name "Net-(LED10-C)") (class "Default")
      (node (ref "LED10") (pin "K") (pinfunction "C_K") (pintype "passive"))
      (node (ref "RN2") (pin "8") (pinfunction "8_8") (pintype "passive"))
    )
    (net (code "94") (name "Net-(LED11-C)") (class "Default")
      (node (ref "LED11") (pin "K") (pinfunction "C_K") (pintype "passive"))
      (node (ref "RN2") (pin "7") (pinfunction "7_7") (pintype "passive"))
    )
    (net (code "95") (name "Net-(LED12-C)") (class "Default")
      (node (ref "LED12") (pin "K") (pinfunction "C_K") (pintype "passive"))
      (node (ref "RN2") (pin "6") (pinfunction "6_6") (pintype "passive"))
    )
    (net (code "96") (name "Net-(LED13-C)") (class "Default")
      (node (ref "LED13") (pin "K") (pinfunction "C_K") (pintype "passive"))
      (node (ref "RN2") (pin "5") (pinfunction "5_5") (pintype "passive"))
    )
    (net (code "97") (name "Net-(LED14-C)") (class "Default")
      (node (ref "LED14") (pin "K") (pinfunction "C_K") (pintype "passive"))
      (node (ref "RN2") (pin "4") (pinfunction "4_4") (pintype "passive"))
    )
    (net (code "98") (name "Net-(LED15-C)") (class "Default")
      (node (ref "LED15") (pin "K") (pinfunction "C_K") (pintype "passive"))
      (node (ref "RN2") (pin "3") (pinfunction "3_3") (pintype "passive"))
    )
    (net (code "99") (name "Net-(LED16-C)") (class "Default")
      (node (ref "LED16") (pin "K") (pinfunction "C_K") (pintype "passive"))
      (node (ref "RN2") (pin "2") (pinfunction "2_2") (pintype "passive"))
    )
    (net (code "100") (name "Net-(LED17-C)") (class "Default")
      (node (ref "LED17") (pin "K") (pinfunction "C_K") (pintype "passive"))
      (node (ref "RN3") (pin "9") (pinfunction "9_9") (pintype "passive"))
    )
    (net (code "101") (name "Net-(LED18-C)") (class "Default")
      (node (ref "LED18") (pin "K") (pinfunction "C_K") (pintype "passive"))
      (node (ref "RN3") (pin "8") (pinfunction "8_8") (pintype "passive"))
    )
    (net (code "102") (name "Net-(LED19-C)") (class "Default")
      (node (ref "LED19") (pin "K") (pinfunction "C_K") (pintype "passive"))
      (node (ref "RN3") (pin "7") (pinfunction "7_7") (pintype "passive"))
    )
    (net (code "103") (name "Net-(LED20-C)") (class "Default")
      (node (ref "LED20") (pin "K") (pinfunction "C_K") (pintype "passive"))
      (node (ref "RN3") (pin "6") (pinfunction "6_6") (pintype "passive"))
    )
    (net (code "104") (name "Net-(LED21-C)") (class "Default")
      (node (ref "LED21") (pin "K") (pinfunction "C_K") (pintype "passive"))
      (node (ref "RN3") (pin "5") (pinfunction "5_5") (pintype "passive"))
    )
    (net (code "105") (name "Net-(LED22-C)") (class "Default")
      (node (ref "LED22") (pin "K") (pinfunction "C_K") (pintype "passive"))
      (node (ref "RN3") (pin "4") (pinfunction "4_4") (pintype "passive"))
    )
    (net (code "106") (name "Net-(LED23-C)") (class "Default")
      (node (ref "LED23") (pin "K") (pinfunction "C_K") (pintype "passive"))
      (node (ref "RN3") (pin "3") (pinfunction "3_3") (pintype "passive"))
    )
    (net (code "107") (name "Net-(LED24-C)") (class "Default")
      (node (ref "LED24") (pin "K") (pinfunction "C_K") (pintype "passive"))
      (node (ref "RN3") (pin "2") (pinfunction "2_2") (pintype "passive"))
    )
    (net (code "108") (name "Net-(LED25-C)") (class "Default")
      (node (ref "LED25") (pin "K") (pinfunction "C_K") (pintype "passive"))
      (node (ref "RN4") (pin "9") (pinfunction "9_9") (pintype "passive"))
    )
    (net (code "109") (name "Net-(LED26-C)") (class "Default")
      (node (ref "LED26") (pin "K") (pinfunction "C_K") (pintype "passive"))
      (node (ref "RN4") (pin "8") (pinfunction "8_8") (pintype "passive"))
    )
    (net (code "110") (name "Net-(LED27-C)") (class "Default")
      (node (ref "LED27") (pin "K") (pinfunction "C_K") (pintype "passive"))
      (node (ref "RN4") (pin "7") (pinfunction "7_7") (pintype "passive"))
    )
    (net (code "111") (name "Net-(LED28-C)") (class "Default")
      (node (ref "LED28") (pin "K") (pinfunction "C_K") (pintype "passive"))
      (node (ref "RN4") (pin "6") (pinfunction "6_6") (pintype "passive"))
    )
    (net (code "112") (name "Net-(LED29-C)") (class "Default")
      (node (ref "LED29") (pin "K") (pinfunction "C_K") (pintype "passive"))
      (node (ref "RN4") (pin "5") (pinfunction "5_5") (pintype "passive"))
    )
    (net (code "113") (name "Net-(LED30-C)") (class "Default")
      (node (ref "LED30") (pin "K") (pinfunction "C_K") (pintype "passive"))
      (node (ref "RN4") (pin "4") (pinfunction "4_4") (pintype "passive"))
    )
    (net (code "114") (name "Net-(LED31-C)") (class "Default")
      (node (ref "LED31") (pin "K") (pinfunction "C_K") (pintype "passive"))
      (node (ref "RN4") (pin "3") (pinfunction "3_3") (pintype "passive"))
    )
    (net (code "115") (name "Net-(LED32-C)") (class "Default")
      (node (ref "LED32") (pin "K") (pinfunction "C_K") (pintype "passive"))
      (node (ref "RN4") (pin "2") (pinfunction "2_2") (pintype "passive"))
    )
    (net (code "116") (name "Net-(LED33-C)") (class "Default")
      (node (ref "LED33") (pin "K") (pinfunction "C_K") (pintype "passive"))
      (node (ref "RN5") (pin "9") (pinfunction "9_9") (pintype "passive"))
    )
    (net (code "117") (name "Net-(LED34-C)") (class "Default")
      (node (ref "LED34") (pin "K") (pinfunction "C_K") (pintype "passive"))
      (node (ref "RN5") (pin "8") (pinfunction "8_8") (pintype "passive"))
    )
    (net (code "118") (name "Net-(LED35-C)") (class "Default")
      (node (ref "LED35") (pin "K") (pinfunction "C_K") (pintype "passive"))
      (node (ref "RN5") (pin "7") (pinfunction "7_7") (pintype "passive"))
    )
    (net (code "119") (name "Net-(LED36-C)") (class "Default")
      (node (ref "LED36") (pin "K") (pinfunction "C_K") (pintype "passive"))
      (node (ref "RN5") (pin "6") (pinfunction "6_6") (pintype "passive"))
    )
    (net (code "120") (name "Net-(LED37-C)") (class "Default")
      (node (ref "LED37") (pin "K") (pinfunction "C_K") (pintype "passive"))
      (node (ref "RN5") (pin "5") (pinfunction "5_5") (pintype "passive"))
    )
    (net (code "121") (name "Net-(LED38-C)") (class "Default")
      (node (ref "LED38") (pin "K") (pinfunction "C_K") (pintype "passive"))
      (node (ref "RN5") (pin "4") (pinfunction "4_4") (pintype "passive"))
    )
    (net (code "122") (name "Net-(LED39-C)") (class "Default")
      (node (ref "LED39") (pin "K") (pinfunction "C_K") (pintype "passive"))
      (node (ref "RN5") (pin "3") (pinfunction "3_3") (pintype "passive"))
    )
    (net (code "123") (name "Net-(LED40-C)") (class "Default")
      (node (ref "LED40") (pin "K") (pinfunction "C_K") (pintype "passive"))
      (node (ref "RN5") (pin "2") (pinfunction "2_2") (pintype "passive"))
    )
    (net (code "124") (name "Net-(LED41-C)") (class "Default")
      (node (ref "LED41") (pin "K") (pinfunction "C_K") (pintype "passive"))
      (node (ref "RN6") (pin "9") (pinfunction "9_9") (pintype "passive"))
    )
    (net (code "125") (name "Net-(LED42-C)") (class "Default")
      (node (ref "LED42") (pin "K") (pinfunction "C_K") (pintype "passive"))
      (node (ref "RN6") (pin "8") (pinfunction "8_8") (pintype "passive"))
    )
    (net (code "126") (name "Net-(LED43-C)") (class "Default")
      (node (ref "LED43") (pin "K") (pinfunction "C_K") (pintype "passive"))
      (node (ref "RN6") (pin "7") (pinfunction "7_7") (pintype "passive"))
    )
    (net (code "127") (name "Net-(LED44-C)") (class "Default")
      (node (ref "LED44") (pin "K") (pinfunction "C_K") (pintype "passive"))
      (node (ref "RN6") (pin "6") (pinfunction "6_6") (pintype "passive"))
    )
    (net (code "128") (name "Net-(LED45-C)") (class "Default")
      (node (ref "LED45") (pin "K") (pinfunction "C_K") (pintype "passive"))
      (node (ref "RN6") (pin "5") (pinfunction "5_5") (pintype "passive"))
    )
    (net (code "129") (name "Net-(LED46-C)") (class "Default")
      (node (ref "LED46") (pin "K") (pinfunction "C_K") (pintype "passive"))
      (node (ref "RN6") (pin "4") (pinfunction "4_4") (pintype "passive"))
    )
    (net (code "130") (name "Net-(LED47-C)") (class "Default")
      (node (ref "LED47") (pin "K") (pinfunction "C_K") (pintype "passive"))
      (node (ref "RN6") (pin "3") (pinfunction "3_3") (pintype "passive"))
    )
    (net (code "131") (name "Net-(LED48-C)") (class "Default")
      (node (ref "LED48") (pin "K") (pinfunction "C_K") (pintype "passive"))
      (node (ref "RN6") (pin "2") (pinfunction "2_2") (pintype "passive"))
    )
    (net (code "132") (name "Net-(LED49-C)") (class "Default")
      (node (ref "LED49") (pin "K") (pinfunction "C_K") (pintype "passive"))
      (node (ref "R1") (pin "2") (pinfunction "2_2") (pintype "passive"))
    )
    (net (code "133") (name "Net-(LED50-C)") (class "Default")
      (node (ref "LED50") (pin "K") (pinfunction "C_K") (pintype "passive"))
      (node (ref "R2") (pin "2") (pinfunction "2_2") (pintype "passive"))
    )
    (net (code "134") (name "Net-(LED51-C)") (class "Default")
      (node (ref "LED51") (pin "K") (pinfunction "C_K") (pintype "passive"))
      (node (ref "R3") (pin "2") (pinfunction "2_2") (pintype "passive"))
    )
    (net (code "135") (name "VCC") (class "Default")
      (node (ref "C1") (pin "1") (pinfunction "1_1") (pintype "passive"))
      (node (ref "C2") (pin "1") (pinfunction "1_1") (pintype "passive"))
      (node (ref "C3") (pin "1") (pinfunction "1_1") (pintype "passive"))
      (node (ref "C4") (pin "1") (pinfunction "1_1") (pintype "passive"))
      (node (ref "C5") (pin "1") (pinfunction "1_1") (pintype "passive"))
      (node (ref "C6") (pin "1") (pinfunction "1_1") (pintype "passive"))
      (node (ref "C7") (pin "1") (pinfunction "1_1") (pintype "passive"))
      (node (ref "CON3") (pin "13") (pinfunction "13_13") (pintype "passive"))
      (node (ref "CON3") (pin "14") (pinfunction "14_14") (pintype "passive"))
      (node (ref "CON3") (pin "15") (pinfunction "15_15") (pintype "passive"))
      (node (ref "CON3") (pin "16") (pinfunction "16_16") (pintype "passive"))
    )
    (net (code "136") (name "unconnected-(CON2-Pad1)") (class "Default")
      (node (ref "CON2") (pin "1") (pinfunction "1_1") (pintype "passive"))
    )
    (net (code "137") (name "unconnected-(CON2-Pad5)") (class "Default")
      (node (ref "CON2") (pin "5") (pinfunction "5_5") (pintype "passive"))
    )
    (net (code "138") (name "unconnected-(CON2-Pad6)") (class "Default")
      (node (ref "CON2") (pin "6") (pinfunction "6_6") (pintype "passive"))
    )
    (net (code "139") (name "unconnected-(CON2-Pad7)") (class "Default")
      (node (ref "CON2") (pin "7") (pinfunction "7_7") (pintype "passive"))
    )
    (net (code "140") (name "unconnected-(CON2-Pad8)") (class "Default")
      (node (ref "CON2") (pin "8") (pinfunction "8_8") (pintype "passive"))
    )
    (net (code "141") (name "unconnected-(CON2-Pad9)") (class "Default")
      (node (ref "CON2") (pin "9") (pinfunction "9_9") (pintype "passive"))
    )
    (net (code "142") (name "unconnected-(CON2-Pad10)") (class "Default")
      (node (ref "CON2") (pin "10") (pinfunction "10_10") (pintype "passive"))
    )
    (net (code "143") (name "unconnected-(CON2-Pad11)") (class "Default")
      (node (ref "CON2") (pin "11") (pinfunction "11_11") (pintype "passive"))
    )
    (net (code "144") (name "unconnected-(CON2-Pad12)") (class "Default")
      (node (ref "CON2") (pin "12") (pinfunction "12_12") (pintype "passive"))
    )
    (net (code "145") (name "unconnected-(CON2-Pad13)") (class "Default")
      (node (ref "CON2") (pin "13") (pinfunction "13_13") (pintype "passive"))
    )
    (net (code "146") (name "unconnected-(CON2-Pad14)") (class "Default")
      (node (ref "CON2") (pin "14") (pinfunction "14_14") (pintype "passive"))
    )
    (net (code "147") (name "unconnected-(CON2-Pad15)") (class "Default")
      (node (ref "CON2") (pin "15") (pinfunction "15_15") (pintype "passive"))
    )
    (net (code "148") (name "unconnected-(CON2-Pad16)") (class "Default")
      (node (ref "CON2") (pin "16") (pinfunction "16_16") (pintype "passive"))
    )
    (net (code "149") (name "unconnected-(CON2-Pad17)") (class "Default")
      (node (ref "CON2") (pin "17") (pinfunction "17_17") (pintype "passive"))
    )
    (net (code "150") (name "unconnected-(CON2-Pad18)") (class "Default")
      (node (ref "CON2") (pin "18") (pinfunction "18_18") (pintype "passive"))
    )
    (net (code "151") (name "unconnected-(CON2-Pad19)") (class "Default")
      (node (ref "CON2") (pin "19") (pinfunction "19_19") (pintype "passive"))
    )
    (net (code "152") (name "unconnected-(CON2-Pad20)") (class "Default")
      (node (ref "CON2") (pin "20") (pinfunction "20_20") (pintype "passive"))
    )
    (net (code "153") (name "unconnected-(CON4-Pad1)") (class "Default")
      (node (ref "CON4") (pin "1") (pinfunction "1_1") (pintype "passive"))
    )
    (net (code "154") (name "unconnected-(CON4-Pad2)") (class "Default")
      (node (ref "CON4") (pin "2") (pinfunction "2_2") (pintype "passive"))
    )
    (net (code "155") (name "unconnected-(CON4-Pad3)") (class "Default")
      (node (ref "CON4") (pin "3") (pinfunction "3_3") (pintype "passive"))
    )
    (net (code "156") (name "unconnected-(CON4-Pad5)") (class "Default")
      (node (ref "CON4") (pin "5") (pinfunction "5_5") (pintype "passive"))
    )
    (net (code "157") (name "unconnected-(CON4-Pad7)") (class "Default")
      (node (ref "CON4") (pin "7") (pinfunction "7_7") (pintype "passive"))
    )
    (net (code "158") (name "unconnected-(CON4-Pad9)") (class "Default")
      (node (ref "CON4") (pin "9") (pinfunction "9_9") (pintype "passive"))
    )
    (net (code "159") (name "unconnected-(CON4-Pad11)") (class "Default")
      (node (ref "CON4") (pin "11") (pinfunction "11_11") (pintype "passive"))
    )
    (net (code "160") (name "unconnected-(CON4-Pad12)") (class "Default")
      (node (ref "CON4") (pin "12") (pinfunction "12_12") (pintype "passive"))
    )
    (net (code "161") (name "unconnected-(CON4-Pad13)") (class "Default")
      (node (ref "CON4") (pin "13") (pinfunction "13_13") (pintype "passive"))
    )
    (net (code "162") (name "unconnected-(CON4-Pad14)") (class "Default")
      (node (ref "CON4") (pin "14") (pinfunction "14_14") (pintype "passive"))
    )
    (net (code "163") (name "unconnected-(IC5A-Y4-Pad15)") (class "Default")
      (node (ref "IC5") (pin "15") (pinfunction "Y4_15") (pintype "tri_state"))
    )
    (net (code "164") (name "unconnected-(IC5A-Y5-Pad14)") (class "Default")
      (node (ref "IC5") (pin "14") (pinfunction "Y5_14") (pintype "tri_state"))
    )
    (net (code "165") (name "unconnected-(IC5A-Y6-Pad13)") (class "Default")
      (node (ref "IC5") (pin "13") (pinfunction "Y6_13") (pintype "tri_state"))
    )
    (net (code "166") (name "unconnected-(IC5A-Y7-Pad12)") (class "Default")
      (node (ref "IC5") (pin "12") (pinfunction "Y7_12") (pintype "tri_state"))
    )
    (net (code "167") (name "unconnected-(IC5A-Y8-Pad11)") (class "Default")
      (node (ref "IC5") (pin "11") (pinfunction "Y8_11") (pintype "tri_state"))
    )
  )
)
